# POWERAMP.net
KiCad netlist of a schematic drawn in Altium Designer
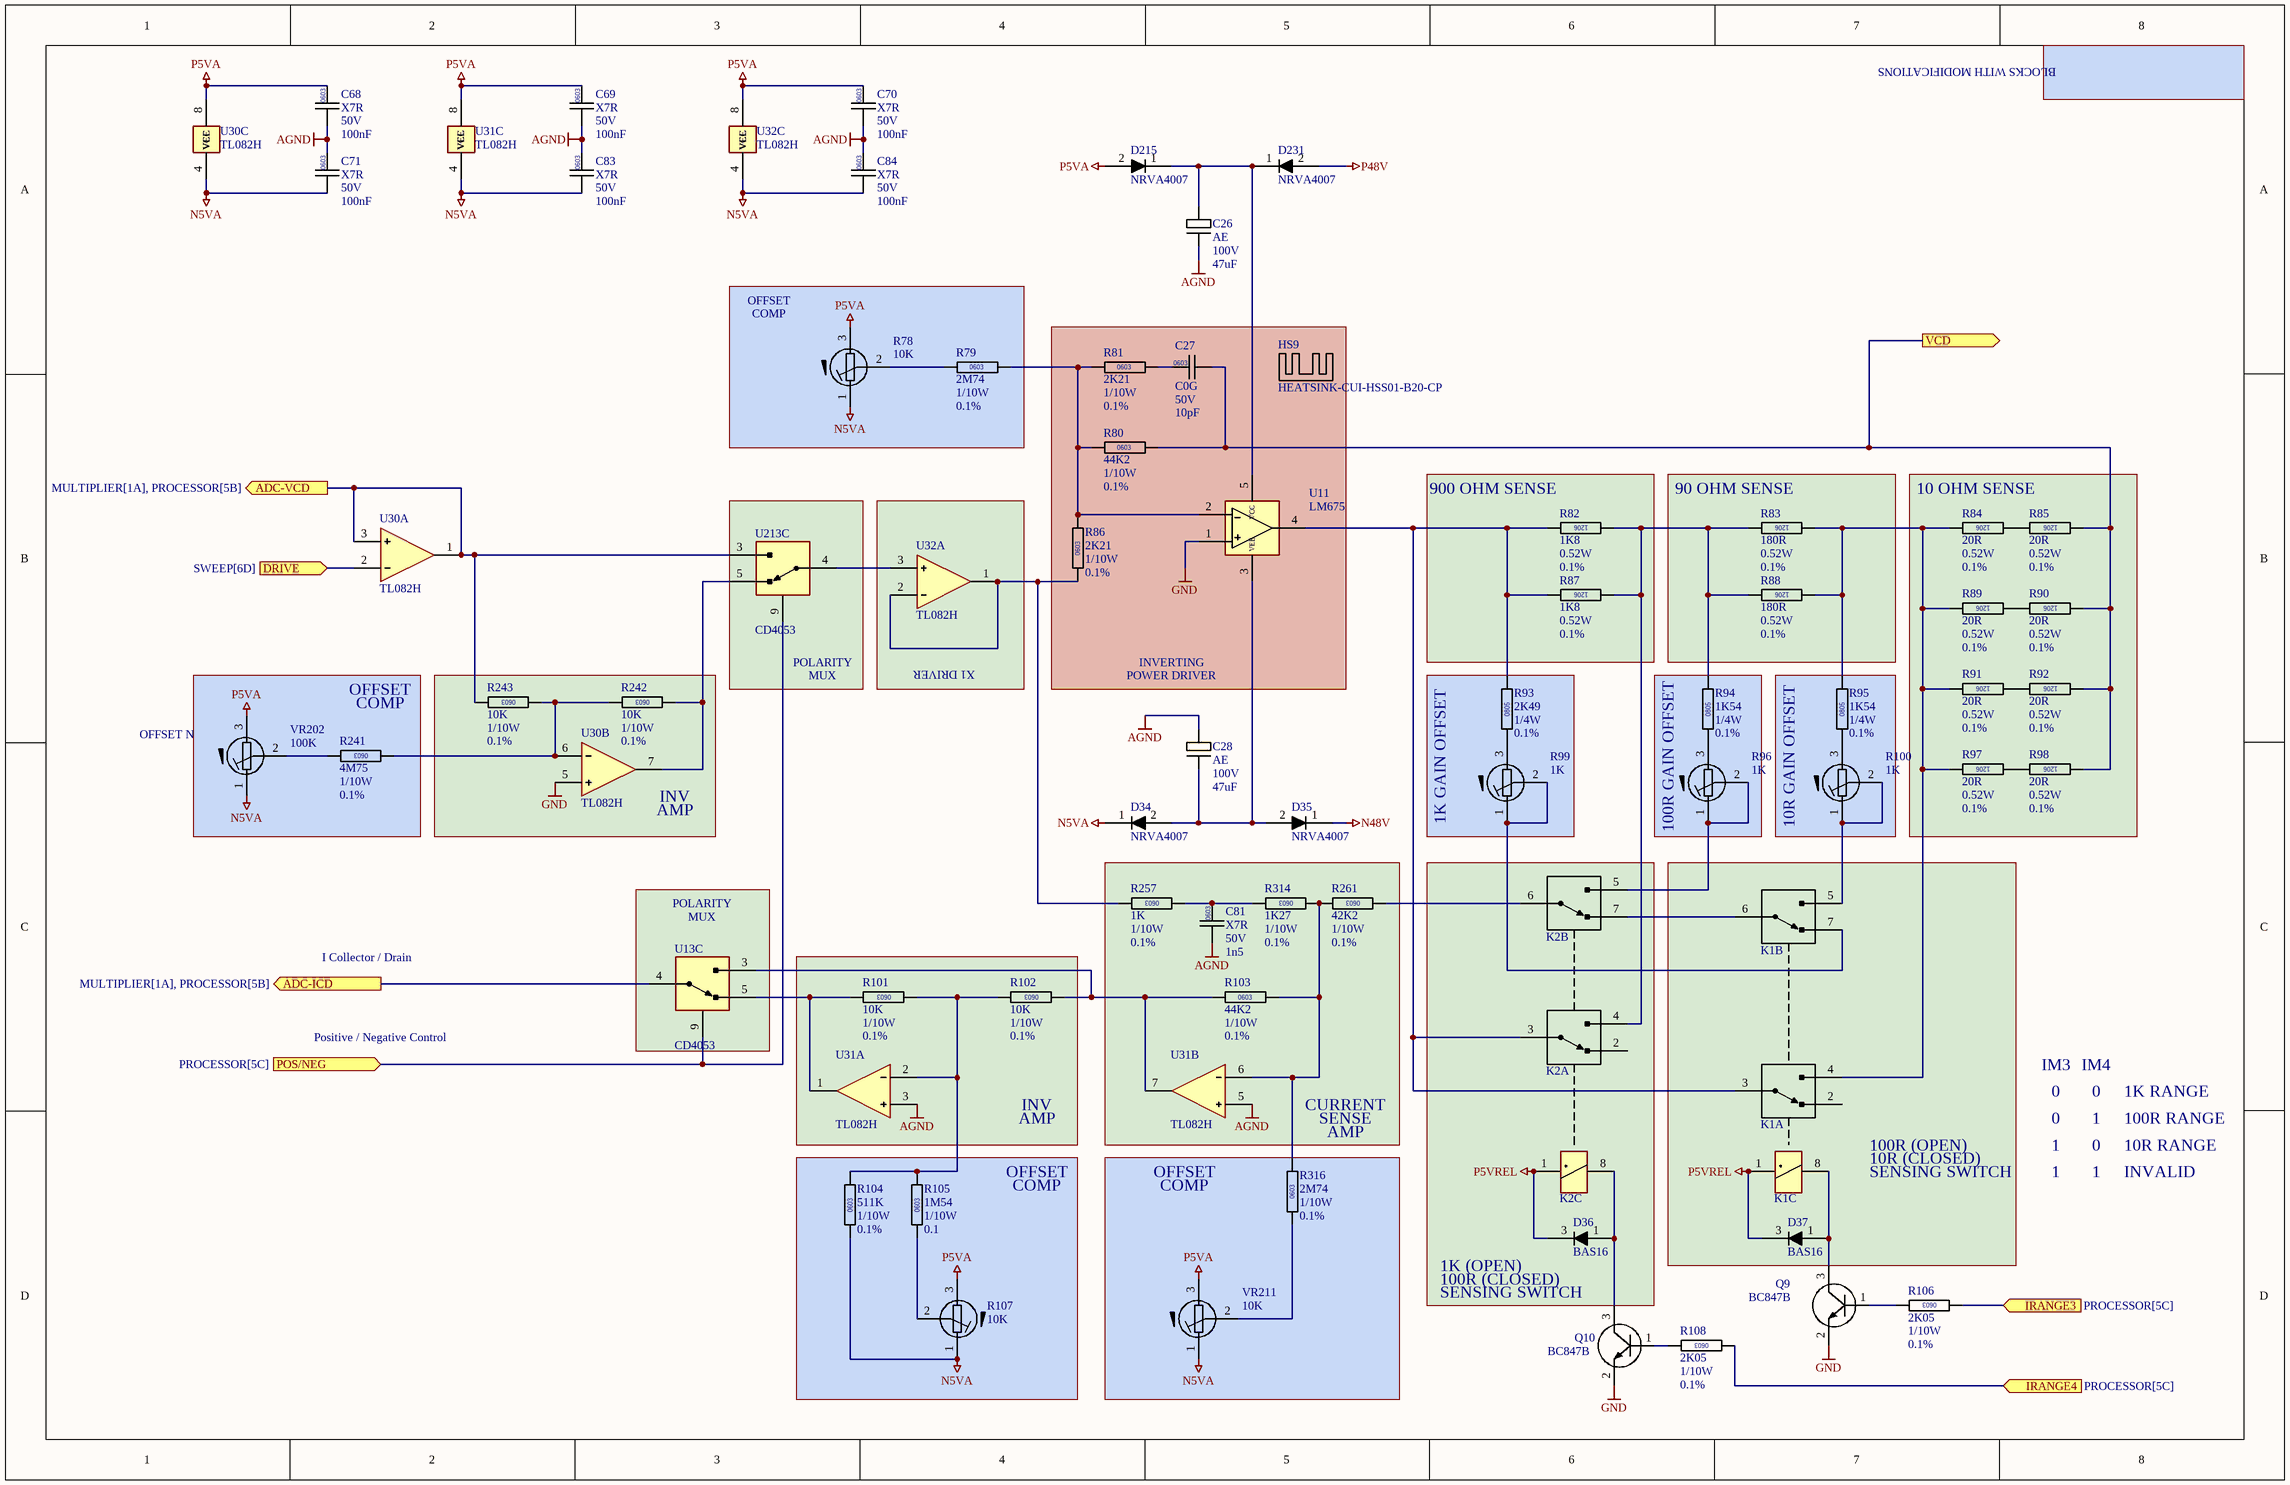
[diagram p0: POWERAMP.SchDoc]

(export (version "E")
  (design (tool "Eeschema 10.0.6"))
  (components
    (comp (ref "C26")
      (value "CAP0603")
      (footprint "CAPAE-KEMET-ESL476M100AH9AA")
      (description "CAPACITOR,ALU,47uF,100V,TH,P5mm,D10mm,H14mm")
      (fields
        (field (name "DIELECTRIC") "AE")
        (field (name "VOLTAGE") "100V")
        (field (name "CAPACITANCE") "47uF")
      )
      (libsource (lib "CAPACITORS") (part "CAPP-AE-47uF-100V-TH050P100D140H"))
    )
    (comp (ref "C27")
      (value "CAP0603")
      (footprint "CAPC0603")
      (description "CAPACITOR,CERAMIC,10pF,50V,C0G,0603")
      (fields
        (field (name "DIELECTRIC") "C0G")
        (field (name "VOLTAGE") "50V")
        (field (name "CAPACITANCE") "10pF")
      )
      (libsource (lib "CAPACITORS") (part "CAPC-0603-10PF-50V-C0G"))
    )
    (comp (ref "C28")
      (value "CAP0603")
      (footprint "CAPAE-KEMET-ESL476M100AH9AA")
      (description "CAPACITOR,ALU,47uF,100V,TH,P5mm,D10mm,H14mm")
      (fields
        (field (name "DIELECTRIC") "AE")
        (field (name "VOLTAGE") "100V")
        (field (name "CAPACITANCE") "47uF")
      )
      (libsource (lib "CAPACITORS") (part "CAPP-AE-47uF-100V-TH050P100D140H"))
    )
    (comp (ref "C68")
      (value "CAP0603")
      (footprint "CAPC0603")
      (description "CAPACITOR,CERAMIC,100nF,50V,X7R,0603")
      (fields
        (field (name "DIELECTRIC") "X7R")
        (field (name "VOLTAGE") "50V")
        (field (name "CAPACITANCE") "100nF")
      )
      (libsource (lib "CAPACITORS") (part "CAPC-0603-100nF-50V-X7R"))
    )
    (comp (ref "C69")
      (value "CAP0603")
      (footprint "CAPC0603")
      (description "CAPACITOR,CERAMIC,100nF,50V,X7R,0603")
      (fields
        (field (name "DIELECTRIC") "X7R")
        (field (name "VOLTAGE") "50V")
        (field (name "CAPACITANCE") "100nF")
      )
      (libsource (lib "CAPACITORS") (part "CAPC-0603-100nF-50V-X7R"))
    )
    (comp (ref "C70")
      (value "CAP0603")
      (footprint "CAPC0603")
      (description "CAPACITOR,CERAMIC,100nF,50V,X7R,0603")
      (fields
        (field (name "DIELECTRIC") "X7R")
        (field (name "VOLTAGE") "50V")
        (field (name "CAPACITANCE") "100nF")
      )
      (libsource (lib "CAPACITORS") (part "CAPC-0603-100nF-50V-X7R"))
    )
    (comp (ref "C71")
      (value "CAP0603")
      (footprint "CAPC0603")
      (description "CAPACITOR,CERAMIC,100nF,50V,X7R,0603")
      (fields
        (field (name "DIELECTRIC") "X7R")
        (field (name "VOLTAGE") "50V")
        (field (name "CAPACITANCE") "100nF")
      )
      (libsource (lib "CAPACITORS") (part "CAPC-0603-100nF-50V-X7R"))
    )
    (comp (ref "C81")
      (value "CAP0603")
      (footprint "CAPC0603")
      (description "CAPACITOR,CERAMIC,1n5,50V,X7R,0603")
      (fields
        (field (name "DIELECTRIC") "X7R")
        (field (name "VOLTAGE") "50V")
        (field (name "CAPACITANCE") "1n5")
      )
      (libsource (lib "CAPACITORS") (part "CAPC-0603-1n5-50V-X7R"))
    )
    (comp (ref "C83")
      (value "CAP0603")
      (footprint "CAPC0603")
      (description "CAPACITOR,CERAMIC,100nF,50V,X7R,0603")
      (fields
        (field (name "DIELECTRIC") "X7R")
        (field (name "VOLTAGE") "50V")
        (field (name "CAPACITANCE") "100nF")
      )
      (libsource (lib "CAPACITORS") (part "CAPC-0603-100nF-50V-X7R"))
    )
    (comp (ref "C84")
      (value "CAP0603")
      (footprint "CAPC0603")
      (description "CAPACITOR,CERAMIC,100nF,50V,X7R,0603")
      (fields
        (field (name "DIELECTRIC") "X7R")
        (field (name "VOLTAGE") "50V")
        (field (name "CAPACITANCE") "100nF")
      )
      (libsource (lib "CAPACITORS") (part "CAPC-0603-100nF-50V-X7R"))
    )
    (comp (ref "D34")
      (value "NRVA4007")
      (footprint "DO214AC")
      (description "DIODE,RECTIFIER,1000V,1A,ONSEMI,NRVA4007,SMA")
      (libsource (lib "DIODES") (part "DIODE-ONSEMI-NRVA4007T3G"))
    )
    (comp (ref "D35")
      (value "NRVA4007")
      (footprint "DO214AC")
      (description "DIODE,RECTIFIER,1000V,1A,ONSEMI,NRVA4007,SMA")
      (libsource (lib "DIODES") (part "DIODE-ONSEMI-NRVA4007T3G"))
    )
    (comp (ref "D36")
      (value "BAS16")
      (footprint "SOT23")
      (description "DIODE,RECTIFIER,75V,0.3A,BAS16,SOT23")
      (libsource (lib "DIODES") (part "DIODE-RECTIFIER-DIODES-BAS16-SOT23"))
    )
    (comp (ref "D37")
      (value "BAS16")
      (footprint "SOT23")
      (description "DIODE,RECTIFIER,75V,0.3A,BAS16,SOT23")
      (libsource (lib "DIODES") (part "DIODE-RECTIFIER-DIODES-BAS16-SOT23"))
    )
    (comp (ref "D215")
      (value "NRVA4007")
      (footprint "DO214AC")
      (description "DIODE,RECTIFIER,1000V,1A,ONSEMI,NRVA4007,SMA")
      (libsource (lib "DIODES") (part "DIODE-ONSEMI-NRVA4007T3G"))
    )
    (comp (ref "D231")
      (value "NRVA4007")
      (footprint "DO214AC")
      (description "DIODE,RECTIFIER,1000V,1A,ONSEMI,NRVA4007,SMA")
      (libsource (lib "DIODES") (part "DIODE-ONSEMI-NRVA4007T3G"))
    )
    (comp (ref "HS9")
      (value "HEATSINK-CUI-HSS01-B20-CP")
      (footprint "HEATSINK-CUI-HSS01-B20-CP")
      (description "HEATSINKSTAMPED,CLIP-ON,BOARDMOUNT,3W,25C/W,CUI,HSS01-B20-CP")
      (libsource (lib "HEATSINK") (part "HEATSINK-CUI-HSS01-B20-CP"))
    )
    (comp (ref "K1")
      (value "RELAY-KEMET-UA2-5NJ")
      (footprint "RELAY-KEMET-UA2-5NJ")
      (description "RELAY,DPDT,1A,250VAC,220VDC,5V COIL,KEMET,UA2-5NJ")
      (libsource (lib "RELAYS") (part "RELAY-KEMET-UA2-5NJ"))
    )
    (comp (ref "K2")
      (value "RELAY-KEMET-UA2-5NJ")
      (footprint "RELAY-KEMET-UA2-5NJ")
      (description "RELAY,DPDT,1A,250VAC,220VDC,5V COIL,KEMET,UA2-5NJ")
      (libsource (lib "") (part "RELAY-KEMET-UA2-5NJ_1"))
    )
    (comp (ref "Q9")
      (value "BC847B")
      (footprint "SOT23")
      (description "XSTR,NPN,45V,0.1A,,BC847B,SOT23")
      (libsource (lib "TRANSISTORS") (part "XSTR-NPN-BC847"))
    )
    (comp (ref "Q10")
      (value "BC847B")
      (footprint "SOT23")
      (description "XSTR,NPN,45V,0.1A,,BC847B,SOT23")
      (libsource (lib "TRANSISTORS") (part "XSTR-NPN-BC847"))
    )
    (comp (ref "R78")
      (value "10K")
      (footprint "TRIMMER-BOURNS-3214X")
      (description "RESISTOR,MULTITURN,VERTICAL,5T,10K")
      (fields (field (name "Comment") "TRIMMER-BOURNS-3214X-1-103E"))
      (libsource (lib "RESISTORS") (part "TRIMMER-BOURNS-3214X-1-103E"))
    )
    (comp (ref "R79")
      (value "2M74")
      (footprint "RESC0603")
      (description "RESISTOR,2M74,0.1%,100mW,0603 (1608)")
      (fields
        (field (name "POWER") "1/10W")
        (field (name "TOLERANCE") "0.1%")
        (field (name "Comment") "RESC0603")
      )
      (libsource (lib "RESISTORS") (part "RESC-0603-2M74-0.1%-1/10W"))
    )
    (comp (ref "R80")
      (value "44K2")
      (footprint "RESC0603")
      (description "RESISTOR,44K2,0.1%,100mW,0603 (1608)")
      (fields
        (field (name "POWER") "1/10W")
        (field (name "TOLERANCE") "0.1%")
        (field (name "Comment") "RESC0603")
      )
      (libsource (lib "RESISTORS") (part "RESC-0603-44K2-0.1%-1/10W"))
    )
    (comp (ref "R81")
      (value "2K21")
      (footprint "RESC0603")
      (description "RESISTOR,2K21,0.1%,100mW,0603 (1608)")
      (fields
        (field (name "POWER") "1/10W")
        (field (name "TOLERANCE") "0.1%")
        (field (name "Comment") "RESC0603")
      )
      (libsource (lib "RESISTORS") (part "RESC-0603-2K21-0.1%-1/10W"))
    )
    (comp (ref "R82")
      (value "1K8")
      (footprint "RESC1206")
      (description "RESISTOR,1K8,1206,0.1%,520mW,1206")
      (fields
        (field (name "POWER") "0.52W")
        (field (name "TOLERANCE") "0.1%")
        (field (name "Comment") "RESC1206")
      )
      (libsource (lib "RESISTORS") (part "RESC-1206-1K8-0.1%-1/2W"))
    )
    (comp (ref "R83")
      (value "180R")
      (footprint "RESC1206")
      (description "RESISTOR,180,1206,0.1%,520mW,1206")
      (fields
        (field (name "POWER") "0.52W")
        (field (name "TOLERANCE") "0.1%")
        (field (name "Comment") "RESC1206")
      )
      (libsource (lib "RESISTORS") (part "RESC-1206-180R-0.1%-1/2W"))
    )
    (comp (ref "R84")
      (value "20R")
      (footprint "RESC1206")
      (description "RESISTOR,20R,1206,0.1%,520mW,1206")
      (fields
        (field (name "POWER") "0.52W")
        (field (name "TOLERANCE") "0.1%")
        (field (name "Comment") "RESC1206")
      )
      (libsource (lib "RESISTORS") (part "RESC-1206-20R-0.1%-1/2W"))
    )
    (comp (ref "R85")
      (value "20R")
      (footprint "RESC1206")
      (description "RESISTOR,20R,1206,0.1%,520mW,1206")
      (fields
        (field (name "POWER") "0.52W")
        (field (name "TOLERANCE") "0.1%")
        (field (name "Comment") "RESC1206")
      )
      (libsource (lib "RESISTORS") (part "RESC-1206-20R-0.1%-1/2W"))
    )
    (comp (ref "R86")
      (value "2K21")
      (footprint "RESC0603")
      (description "RESISTOR,2K21,0.1%,100mW,0603 (1608)")
      (fields
        (field (name "POWER") "1/10W")
        (field (name "TOLERANCE") "0.1%")
        (field (name "Comment") "RESC0603")
      )
      (libsource (lib "RESISTORS") (part "RESC-0603-2K21-0.1%-1/10W"))
    )
    (comp (ref "R87")
      (value "1K8")
      (footprint "RESC1206")
      (description "RESISTOR,1K8,1206,0.1%,520mW,1206")
      (fields
        (field (name "POWER") "0.52W")
        (field (name "TOLERANCE") "0.1%")
        (field (name "Comment") "RESC1206")
      )
      (libsource (lib "RESISTORS") (part "RESC-1206-1K8-0.1%-1/2W"))
    )
    (comp (ref "R88")
      (value "180R")
      (footprint "RESC1206")
      (description "RESISTOR,180,1206,0.1%,520mW,1206")
      (fields
        (field (name "POWER") "0.52W")
        (field (name "TOLERANCE") "0.1%")
        (field (name "Comment") "RESC1206")
      )
      (libsource (lib "RESISTORS") (part "RESC-1206-180R-0.1%-1/2W"))
    )
    (comp (ref "R89")
      (value "20R")
      (footprint "RESC1206")
      (description "RESISTOR,20R,1206,0.1%,520mW,1206")
      (fields
        (field (name "POWER") "0.52W")
        (field (name "TOLERANCE") "0.1%")
        (field (name "Comment") "RESC1206")
      )
      (libsource (lib "RESISTORS") (part "RESC-1206-20R-0.1%-1/2W"))
    )
    (comp (ref "R90")
      (value "20R")
      (footprint "RESC1206")
      (description "RESISTOR,20R,1206,0.1%,520mW,1206")
      (fields
        (field (name "POWER") "0.52W")
        (field (name "TOLERANCE") "0.1%")
        (field (name "Comment") "RESC1206")
      )
      (libsource (lib "RESISTORS") (part "RESC-1206-20R-0.1%-1/2W"))
    )
    (comp (ref "R91")
      (value "20R")
      (footprint "RESC1206")
      (description "RESISTOR,20R,1206,0.1%,520mW,1206")
      (fields
        (field (name "POWER") "0.52W")
        (field (name "TOLERANCE") "0.1%")
        (field (name "Comment") "RESC1206")
      )
      (libsource (lib "RESISTORS") (part "RESC-1206-20R-0.1%-1/2W"))
    )
    (comp (ref "R92")
      (value "20R")
      (footprint "RESC1206")
      (description "RESISTOR,20R,1206,0.1%,520mW,1206")
      (fields
        (field (name "POWER") "0.52W")
        (field (name "TOLERANCE") "0.1%")
        (field (name "Comment") "RESC1206")
      )
      (libsource (lib "RESISTORS") (part "RESC-1206-20R-0.1%-1/2W"))
    )
    (comp (ref "R93")
      (value "2K49")
      (footprint "RESC0805")
      (description "RESISTOR,2K49,0.1%,250mW,0805")
      (fields
        (field (name "POWER") "1/4W")
        (field (name "TOLERANCE") "0.1%")
        (field (name "Comment") "RESC0805")
      )
      (libsource (lib "RESISTORS") (part "RESC-0805-2K49-0.1%-1/4W"))
    )
    (comp (ref "R94")
      (value "1K54")
      (footprint "RESC0805")
      (description "RESISTOR,1K54,0.1%,250mW,0805")
      (fields
        (field (name "POWER") "1/4W")
        (field (name "TOLERANCE") "0.1%")
        (field (name "Comment") "RESC0805")
      )
      (libsource (lib "RESISTORS") (part "RESC-0805-1K54-0.1%-1/4W"))
    )
    (comp (ref "R95")
      (value "1K54")
      (footprint "RESC0805")
      (description "RESISTOR,1K54,0.1%,250mW,0805")
      (fields
        (field (name "POWER") "1/4W")
        (field (name "TOLERANCE") "0.1%")
        (field (name "Comment") "RESC0805")
      )
      (libsource (lib "RESISTORS") (part "RESC-0805-1K54-0.1%-1/4W"))
    )
    (comp (ref "R96")
      (value "1K")
      (footprint "TRIMMER-BOURNS-3214X")
      (description "RESISTOR,MULTITURN,VERTICAL,5T,1K")
      (fields (field (name "Comment") "TRIMMER-BOURNS-3214X-1-102E"))
      (libsource (lib "RESISTORS") (part "TRIMMER-BOURNS-3214X-1-102E"))
    )
    (comp (ref "R97")
      (value "20R")
      (footprint "RESC1206")
      (description "RESISTOR,20R,1206,0.1%,520mW,1206")
      (fields
        (field (name "POWER") "0.52W")
        (field (name "TOLERANCE") "0.1%")
        (field (name "Comment") "RESC1206")
      )
      (libsource (lib "RESISTORS") (part "RESC-1206-20R-0.1%-1/2W"))
    )
    (comp (ref "R98")
      (value "20R")
      (footprint "RESC1206")
      (description "RESISTOR,20R,1206,0.1%,520mW,1206")
      (fields
        (field (name "POWER") "0.52W")
        (field (name "TOLERANCE") "0.1%")
        (field (name "Comment") "RESC1206")
      )
      (libsource (lib "RESISTORS") (part "RESC-1206-20R-0.1%-1/2W"))
    )
    (comp (ref "R99")
      (value "1K")
      (footprint "TRIMMER-BOURNS-3214X")
      (description "RESISTOR,MULTITURN,VERTICAL,5T,1K")
      (fields (field (name "Comment") "TRIMMER-BOURNS-3214X-1-102E"))
      (libsource (lib "RESISTORS") (part "TRIMMER-BOURNS-3214X-1-102E"))
    )
    (comp (ref "R100")
      (value "1K")
      (footprint "TRIMMER-BOURNS-3214X")
      (description "RESISTOR,MULTITURN,VERTICAL,5T,1K")
      (fields (field (name "Comment") "TRIMMER-BOURNS-3214X-1-102E"))
      (libsource (lib "RESISTORS") (part "TRIMMER-BOURNS-3214X-1-102E"))
    )
    (comp (ref "R101")
      (value "10K")
      (footprint "RESC0603")
      (description "RESISTOR,10K,0.1%,100mW,0603 (1608)")
      (fields
        (field (name "POWER") "1/10W")
        (field (name "TOLERANCE") "0.1%")
        (field (name "Comment") "RESC0603")
      )
      (libsource (lib "RESISTORS") (part "RESC-0603-10K-0.1%-1/10W"))
    )
    (comp (ref "R102")
      (value "10K")
      (footprint "RESC0603")
      (description "RESISTOR,10K,0.1%,100mW,0603 (1608)")
      (fields
        (field (name "POWER") "1/10W")
        (field (name "TOLERANCE") "0.1%")
        (field (name "Comment") "RESC0603")
      )
      (libsource (lib "RESISTORS") (part "RESC-0603-10K-0.1%-1/10W"))
    )
    (comp (ref "R103")
      (value "44K2")
      (footprint "RESC0603")
      (description "RESISTOR,44K2,0.1%,100mW,0603 (1608)")
      (fields
        (field (name "POWER") "1/10W")
        (field (name "TOLERANCE") "0.1%")
        (field (name "Comment") "RESC0603")
      )
      (libsource (lib "RESISTORS") (part "RESC-0603-44K2-0.1%-1/10W"))
    )
    (comp (ref "R104")
      (value "511K")
      (footprint "RESC0603")
      (description "RESISTOR,511K,0.1%,100mW,0603 (1608)")
      (fields
        (field (name "POWER") "1/10W")
        (field (name "TOLERANCE") "0.1%")
        (field (name "Comment") "RESC0603")
      )
      (libsource (lib "RESISTORS") (part "RESC-0603-511K-0.1%-1/10W"))
    )
    (comp (ref "R105")
      (value "1M54")
      (footprint "RESC0603")
      (description "RESISTOR,1M54,0.1%,100mW,0603 (1608)")
      (fields
        (field (name "POWER") "1/10W")
        (field (name "TOLERANCE") "0.1")
        (field (name "Comment") "RESC0603")
      )
      (libsource (lib "RESISTORS") (part "RESC-0603-1M54-0.1%-1/10W"))
    )
    (comp (ref "R106")
      (value "2K05")
      (footprint "RESC0603")
      (description "RESISTOR,2K05,0.11%,100mW,0603 (1608)")
      (fields
        (field (name "POWER") "1/10W")
        (field (name "TOLERANCE") "0.1%")
        (field (name "Comment") "RESC0603")
      )
      (libsource (lib "RESISTORS") (part "RESC-0603-2K05-0.1%-1/10W"))
    )
    (comp (ref "R107")
      (value "10K")
      (footprint "TRIMMER-BOURNS-3214X")
      (description "RESISTOR,MULTITURN,VERTICAL,5T,10K")
      (fields (field (name "Comment") "TRIMMER-BOURNS-3214X-1-103E"))
      (libsource (lib "RESISTORS") (part "TRIMMER-BOURNS-3214X-1-103E"))
    )
    (comp (ref "R108")
      (value "2K05")
      (footprint "RESC0603")
      (description "RESISTOR,2K05,0.11%,100mW,0603 (1608)")
      (fields
        (field (name "POWER") "1/10W")
        (field (name "TOLERANCE") "0.1%")
        (field (name "Comment") "RESC0603")
      )
      (libsource (lib "RESISTORS") (part "RESC-0603-2K05-0.1%-1/10W"))
    )
    (comp (ref "R241")
      (value "4M75")
      (footprint "RESC0603")
      (description "RESISTOR,4M75,0.1%,100mW,0603 (1608)")
      (fields
        (field (name "POWER") "1/10W")
        (field (name "TOLERANCE") "0.1%")
        (field (name "Comment") "RESC0603")
      )
      (libsource (lib "RESISTORS") (part "RESC-0603-4M75-1%-1/10W"))
    )
    (comp (ref "R242")
      (value "10K")
      (footprint "RESC0603")
      (description "RESISTOR,10K,0.1%,100mW,0603 (1608)")
      (fields
        (field (name "POWER") "1/10W")
        (field (name "TOLERANCE") "0.1%")
        (field (name "Comment") "RESC0603")
      )
      (libsource (lib "RESISTORS") (part "RESC-0603-10K-0.1%-1/10W"))
    )
    (comp (ref "R243")
      (value "10K")
      (footprint "RESC0603")
      (description "RESISTOR,10K,0.1%,100mW,0603 (1608)")
      (fields
        (field (name "POWER") "1/10W")
        (field (name "TOLERANCE") "0.1%")
        (field (name "Comment") "RESC0603")
      )
      (libsource (lib "RESISTORS") (part "RESC-0603-10K-0.1%-1/10W"))
    )
    (comp (ref "R257")
      (value "1K")
      (footprint "RESC0603")
      (description "RESISTOR,1K,0.1%,100mW,0603 (1608)")
      (fields
        (field (name "POWER") "1/10W")
        (field (name "TOLERANCE") "0.1%")
        (field (name "Comment") "RESC0603")
      )
      (libsource (lib "RESISTORS") (part "RESC-0603-1K-0.1%-1/10W"))
    )
    (comp (ref "R261")
      (value "42K2")
      (footprint "RESC0603")
      (description "RESISTOR,42K2,0.1%,100mW,0603 (1608)")
      (fields
        (field (name "POWER") "1/10W")
        (field (name "TOLERANCE") "0.1%")
        (field (name "Comment") "RESC0603")
      )
      (libsource (lib "RESISTORS") (part "RESC-0603-42K2-0.1%-1/10W"))
    )
    (comp (ref "R314")
      (value "1K27")
      (footprint "RESC0603")
      (description "RESISTOR,1K27,0.1%,100mW,0603 (1608)")
      (fields
        (field (name "POWER") "1/10W")
        (field (name "TOLERANCE") "0.1%")
        (field (name "Comment") "RESC0603")
      )
      (libsource (lib "RESISTORS") (part "RESC-0603-1K27-0.1%-1/10W"))
    )
    (comp (ref "R316")
      (value "2M74")
      (footprint "RESC0603")
      (description "RESISTOR,2M74,0.1%,100mW,0603 (1608)")
      (fields
        (field (name "POWER") "1/10W")
        (field (name "TOLERANCE") "0.1%")
        (field (name "Comment") "RESC0603")
      )
      (libsource (lib "RESISTORS") (part "RESC-0603-2M74-0.1%-1/10W"))
    )
    (comp (ref "U11")
      (value "LM675")
      (footprint "TO220-5-V")
      (description "IC,OPAMP,SINGLE,POWER,LM675,TO220-5")
      (libsource (lib "IC-OPAMP") (part "IC-TI-LM675-TO220-5"))
    )
    (comp (ref "U13")
      (value "CD4053")
      (footprint "SO127P600-16N")
      (description "IC,LOGIC,CMOS,4XXX,TRIPLE 2:1 MUX,SPLIT BLOCKS")
      (libsource (lib "") (part "IC-TI-CD4053-SPLIT_1"))
    )
    (comp (ref "U30")
      (value "TL082H")
      (footprint "SO127P600-8N")
      (description "IC,OPAMP JFET,DUAL,TL082HIDR,SO8")
      (libsource (lib "") (part "IC-TI-TL082H-SO8_1"))
    )
    (comp (ref "U31")
      (value "TL082H")
      (footprint "SO127P600-8N")
      (description "IC,OPAMP JFET,DUAL,TL082HIDR,SO8")
      (libsource (lib "") (part "IC-TI-TL082H-SO8_2"))
    )
    (comp (ref "U32")
      (value "TL082H")
      (footprint "SO127P600-8N")
      (description "IC,OPAMP JFET,DUAL,TL082HIDR,SO8")
      (libsource (lib "IC-OPAMP") (part "IC-TI-TL082H-SO8"))
    )
    (comp (ref "U213")
      (value "CD4053")
      (footprint "SO127P600-16N")
      (description "IC,LOGIC,CMOS,4XXX,TRIPLE 2:1 MUX,SPLIT BLOCKS")
      (libsource (lib "IC-4XXX") (part "IC-TI-CD4053-SPLIT"))
    )
    (comp (ref "VR202")
      (value "100K")
      (footprint "TRIMMER-BOURNS-3214X")
      (description "RESISTOR,MULTITURN,VERTICAL,5T,100K")
      (fields (field (name "Comment") "TRIMMER-BOURNS-3214X-1-104"))
      (libsource (lib "RESISTORS") (part "TRIMMER-BOURNS-3214X-1-104"))
    )
    (comp (ref "VR211")
      (value "10K")
      (footprint "TRIMMER-BOURNS-3214X")
      (description "RESISTOR,MULTITURN,VERTICAL,5T,10K")
      (fields (field (name "Comment") "TRIMMER-BOURNS-3214X-1-103E"))
      (libsource (lib "RESISTORS") (part "TRIMMER-BOURNS-3214X-1-103E"))
    )
  )
  (nets
    (net (code "1") (name "/ADC-ICD") (class "Default")
      (node (ref "U13") (pin "4") (pinfunction "Y3_4") (pintype "passive"))
    )
    (net (code "2") (name "/ADC-VCD") (class "Default")
      (node (ref "R243") (pin "1") (pintype "passive"))
      (node (ref "U213") (pin "3") (pinfunction "Y_3") (pintype "passive"))
      (node (ref "U30") (pin "1") (pinfunction "O_1") (pintype "passive"))
      (node (ref "U30") (pin "3") (pinfunction "+_3") (pintype "passive"))
    )
    (net (code "3") (name "/DRIVE") (class "Default")
      (node (ref "U30") (pin "2") (pinfunction "-_2") (pintype "passive"))
    )
    (net (code "4") (name "/IRANGE3") (class "Default") (node (ref "R106") (pin "1") (pintype "passive")))
    (net (code "5") (name "/IRANGE4") (class "Default") (node (ref "R108") (pin "1") (pintype "passive")))
    (net (code "6") (name "/POS{slash}NEG") (class "Default")
      (node (ref "U13") (pin "9") (pinfunction "B_9") (pintype "passive"))
      (node (ref "U213") (pin "9") (pinfunction "B_9") (pintype "passive"))
    )
    (net (code "7") (name "/VCD") (class "Default")
      (node (ref "C27") (pin "2") (pintype "passive"))
      (node (ref "R80") (pin "2") (pintype "passive"))
      (node (ref "R85") (pin "2") (pintype "passive"))
      (node (ref "R90") (pin "2") (pintype "passive"))
      (node (ref "R92") (pin "2") (pintype "passive"))
      (node (ref "R98") (pin "2") (pintype "passive"))
    )
    (net (code "8") (name "AGND") (class "Default")
      (node (ref "C26") (pin "2") (pintype "passive"))
      (node (ref "C28") (pin "1") (pintype "passive"))
      (node (ref "C68") (pin "2") (pintype "passive"))
      (node (ref "C69") (pin "2") (pintype "passive"))
      (node (ref "C70") (pin "2") (pintype "passive"))
      (node (ref "C71") (pin "1") (pintype "passive"))
      (node (ref "C81") (pin "2") (pintype "passive"))
      (node (ref "C83") (pin "1") (pintype "passive"))
      (node (ref "C84") (pin "1") (pintype "passive"))
      (node (ref "U31") (pin "3") (pinfunction "+_3") (pintype "passive"))
      (node (ref "U31") (pin "5") (pinfunction "+_5") (pintype "passive"))
    )
    (net (code "9") (name "GND") (class "Default")
      (node (ref "Q10") (pin "2") (pinfunction "E_2") (pintype "passive"))
      (node (ref "Q9") (pin "2") (pinfunction "E_2") (pintype "passive"))
      (node (ref "U11") (pin "1") (pinfunction "+_1") (pintype "passive"))
      (node (ref "U30") (pin "5") (pinfunction "+_5") (pintype "passive"))
    )
    (net (code "10") (name "N5VA") (class "Default")
      (node (ref "C71") (pin "2") (pintype "passive"))
      (node (ref "C83") (pin "2") (pintype "passive"))
      (node (ref "C84") (pin "2") (pintype "passive"))
      (node (ref "D34") (pin "1") (pinfunction "K_1") (pintype "passive"))
      (node (ref "R104") (pin "2") (pintype "passive"))
      (node (ref "R107") (pin "1") (pinfunction "1_1") (pintype "passive"))
      (node (ref "R78") (pin "1") (pinfunction "1_1") (pintype "passive"))
      (node (ref "U30") (pin "4") (pinfunction "VEE_4") (pintype "passive"))
      (node (ref "U31") (pin "4") (pinfunction "VEE_4") (pintype "passive"))
      (node (ref "U32") (pin "4") (pinfunction "VEE_4") (pintype "passive"))
      (node (ref "VR202") (pin "1") (pinfunction "1_1") (pintype "passive"))
      (node (ref "VR211") (pin "1") (pinfunction "1_1") (pintype "passive"))
    )
    (net (code "11") (name "N48V") (class "Default")
      (node (ref "D35") (pin "1") (pinfunction "K_1") (pintype "passive"))
    )
    (net (code "12") (name "Net-(C27-Pad1)") (class "Default")
      (node (ref "C27") (pin "1") (pintype "passive"))
      (node (ref "R81") (pin "2") (pintype "passive"))
    )
    (net (code "13") (name "Net-(C81-Pad1)") (class "Default")
      (node (ref "C81") (pin "1") (pintype "passive"))
      (node (ref "R257") (pin "2") (pintype "passive"))
      (node (ref "R314") (pin "1") (pintype "passive"))
    )
    (net (code "14") (name "Net-(D34-A)") (class "Default")
      (node (ref "C28") (pin "2") (pintype "passive"))
      (node (ref "D34") (pin "2") (pinfunction "A_2") (pintype "passive"))
      (node (ref "D35") (pin "2") (pinfunction "A_2") (pintype "passive"))
      (node (ref "U11") (pin "3") (pinfunction "VEE_3") (pintype "passive"))
    )
    (net (code "15") (name "Net-(D36-A)") (class "Default")
      (node (ref "D36") (pin "1") (pinfunction "A_1") (pintype "passive"))
      (node (ref "K2") (pin "8") (pinfunction "8_8") (pintype "passive"))
      (node (ref "Q10") (pin "3") (pinfunction "C_3") (pintype "passive"))
    )
    (net (code "16") (name "Net-(D37-A)") (class "Default")
      (node (ref "D37") (pin "1") (pinfunction "A_1") (pintype "passive"))
      (node (ref "K1") (pin "8") (pinfunction "8_8") (pintype "passive"))
      (node (ref "Q9") (pin "3") (pinfunction "C_3") (pintype "passive"))
    )
    (net (code "17") (name "Net-(D215-K)") (class "Default")
      (node (ref "C26") (pin "1") (pintype "passive"))
      (node (ref "D215") (pin "1") (pinfunction "K_1") (pintype "passive"))
      (node (ref "D231") (pin "1") (pinfunction "K_1") (pintype "passive"))
      (node (ref "U11") (pin "5") (pinfunction "VCC_5") (pintype "passive"))
    )
    (net (code "18") (name "Net-(K1A-COM)") (class "Default")
      (node (ref "K1") (pin "3") (pinfunction "COM_3") (pintype "passive"))
      (node (ref "K2") (pin "3") (pinfunction "COM_3") (pintype "passive"))
      (node (ref "R82") (pin "1") (pintype "passive"))
      (node (ref "R87") (pin "1") (pintype "passive"))
      (node (ref "R93") (pin "1") (pintype "passive"))
      (node (ref "U11") (pin "4") (pinfunction "OUT_4") (pintype "passive"))
    )
    (net (code "19") (name "Net-(K1A-NO)") (class "Default")
      (node (ref "K1") (pin "4") (pinfunction "NO_4") (pintype "passive"))
      (node (ref "R83") (pin "2") (pintype "passive"))
      (node (ref "R84") (pin "1") (pintype "passive"))
      (node (ref "R88") (pin "2") (pintype "passive"))
      (node (ref "R89") (pin "1") (pintype "passive"))
      (node (ref "R91") (pin "1") (pintype "passive"))
      (node (ref "R95") (pin "2") (pintype "passive"))
      (node (ref "R97") (pin "1") (pintype "passive"))
    )
    (net (code "20") (name "Net-(K1B-COM)") (class "Default")
      (node (ref "K1") (pin "6") (pinfunction "COM_6") (pintype "passive"))
      (node (ref "K2") (pin "7") (pinfunction "NC_7") (pintype "passive"))
    )
    (net (code "21") (name "Net-(K1B-NC)") (class "Default")
      (node (ref "K1") (pin "7") (pinfunction "NC_7") (pintype "passive"))
      (node (ref "R99") (pin "1") (pinfunction "1_1") (pintype "passive"))
      (node (ref "R99") (pin "2") (pinfunction "2_2") (pintype "passive"))
    )
    (net (code "22") (name "Net-(K1B-NO)") (class "Default")
      (node (ref "K1") (pin "5") (pinfunction "NO_5") (pintype "passive"))
      (node (ref "R100") (pin "1") (pinfunction "1_1") (pintype "passive"))
      (node (ref "R100") (pin "2") (pinfunction "2_2") (pintype "passive"))
    )
    (net (code "23") (name "Net-(K2A-NO)") (class "Default")
      (node (ref "K2") (pin "4") (pinfunction "NO_4") (pintype "passive"))
      (node (ref "R82") (pin "2") (pintype "passive"))
      (node (ref "R83") (pin "1") (pintype "passive"))
      (node (ref "R87") (pin "2") (pintype "passive"))
      (node (ref "R88") (pin "1") (pintype "passive"))
      (node (ref "R94") (pin "2") (pintype "passive"))
    )
    (net (code "24") (name "Net-(K2B-COM)") (class "Default")
      (node (ref "K2") (pin "6") (pinfunction "COM_6") (pintype "passive"))
      (node (ref "R261") (pin "2") (pintype "passive"))
    )
    (net (code "25") (name "Net-(K2B-NO)") (class "Default")
      (node (ref "K2") (pin "5") (pinfunction "NO_5") (pintype "passive"))
      (node (ref "R96") (pin "1") (pinfunction "1_1") (pintype "passive"))
      (node (ref "R96") (pin "2") (pinfunction "2_2") (pintype "passive"))
    )
    (net (code "26") (name "Net-(Q9-B)") (class "Default")
      (node (ref "Q9") (pin "1") (pinfunction "B_1") (pintype "passive"))
      (node (ref "R106") (pin "2") (pintype "passive"))
    )
    (net (code "27") (name "Net-(Q10-B)") (class "Default")
      (node (ref "Q10") (pin "1") (pinfunction "B_1") (pintype "passive"))
      (node (ref "R108") (pin "2") (pintype "passive"))
    )
    (net (code "28") (name "Net-(R78-Pad2)") (class "Default")
      (node (ref "R78") (pin "2") (pinfunction "2_2") (pintype "passive"))
      (node (ref "R79") (pin "1") (pintype "passive"))
    )
    (net (code "29") (name "Net-(R84-Pad2)") (class "Default")
      (node (ref "R84") (pin "2") (pintype "passive"))
      (node (ref "R85") (pin "1") (pintype "passive"))
    )
    (net (code "30") (name "Net-(R89-Pad2)") (class "Default")
      (node (ref "R89") (pin "2") (pintype "passive"))
      (node (ref "R90") (pin "1") (pintype "passive"))
    )
    (net (code "31") (name "Net-(R91-Pad2)") (class "Default")
      (node (ref "R91") (pin "2") (pintype "passive"))
      (node (ref "R92") (pin "1") (pintype "passive"))
    )
    (net (code "32") (name "Net-(R93-Pad2)") (class "Default")
      (node (ref "R93") (pin "2") (pintype "passive"))
      (node (ref "R99") (pin "3") (pinfunction "3_3") (pintype "passive"))
    )
    (net (code "33") (name "Net-(R94-Pad1)") (class "Default")
      (node (ref "R94") (pin "1") (pintype "passive"))
      (node (ref "R96") (pin "3") (pinfunction "3_3") (pintype "passive"))
    )
    (net (code "34") (name "Net-(R97-Pad2)") (class "Default")
      (node (ref "R97") (pin "2") (pintype "passive"))
      (node (ref "R98") (pin "1") (pintype "passive"))
    )
    (net (code "35") (name "Net-(R100-Pad3)") (class "Default")
      (node (ref "R100") (pin "3") (pinfunction "3_3") (pintype "passive"))
      (node (ref "R95") (pin "1") (pintype "passive"))
    )
    (net (code "36") (name "Net-(R105-Pad2)") (class "Default")
      (node (ref "R105") (pin "2") (pintype "passive"))
      (node (ref "R107") (pin "2") (pinfunction "2_2") (pintype "passive"))
    )
    (net (code "37") (name "Net-(R241-Pad1)") (class "Default")
      (node (ref "R241") (pin "1") (pintype "passive"))
      (node (ref "VR202") (pin "2") (pinfunction "2_2") (pintype "passive"))
    )
    (net (code "38") (name "Net-(R316-Pad1)") (class "Default")
      (node (ref "R316") (pin "1") (pintype "passive"))
      (node (ref "VR211") (pin "2") (pinfunction "2_2") (pintype "passive"))
    )
    (net (code "39") (name "Net-(U11--)") (class "Default")
      (node (ref "R79") (pin "2") (pintype "passive"))
      (node (ref "R80") (pin "1") (pintype "passive"))
      (node (ref "R81") (pin "1") (pintype "passive"))
      (node (ref "R86") (pin "2") (pintype "passive"))
      (node (ref "U11") (pin "2") (pinfunction "-_2") (pintype "passive"))
    )
    (net (code "40") (name "Net-(U13C-Y)") (class "Default")
      (node (ref "R102") (pin "2") (pintype "passive"))
      (node (ref "R103") (pin "1") (pintype "passive"))
      (node (ref "U13") (pin "3") (pinfunction "Y_3") (pintype "passive"))
      (node (ref "U31") (pin "7") (pinfunction "O_7") (pintype "passive"))
    )
    (net (code "41") (name "Net-(U13C-Y1)") (class "Default")
      (node (ref "R101") (pin "1") (pintype "passive"))
      (node (ref "U13") (pin "5") (pinfunction "Y1_5") (pintype "passive"))
      (node (ref "U31") (pin "1") (pinfunction "O_1") (pintype "passive"))
    )
    (net (code "42") (name "Net-(U30B--)") (class "Default")
      (node (ref "R241") (pin "2") (pintype "passive"))
      (node (ref "R242") (pin "1") (pintype "passive"))
      (node (ref "R243") (pin "2") (pintype "passive"))
      (node (ref "U30") (pin "6") (pinfunction "-_6") (pintype "passive"))
    )
    (net (code "43") (name "Net-(U31A--)") (class "Default")
      (node (ref "R101") (pin "2") (pintype "passive"))
      (node (ref "R102") (pin "1") (pintype "passive"))
      (node (ref "R104") (pin "1") (pintype "passive"))
      (node (ref "R105") (pin "1") (pintype "passive"))
      (node (ref "U31") (pin "2") (pinfunction "-_2") (pintype "passive"))
    )
    (net (code "44") (name "Net-(U31B--)") (class "Default")
      (node (ref "R103") (pin "2") (pintype "passive"))
      (node (ref "R261") (pin "1") (pintype "passive"))
      (node (ref "R314") (pin "2") (pintype "passive"))
      (node (ref "R316") (pin "2") (pintype "passive"))
      (node (ref "U31") (pin "6") (pinfunction "-_6") (pintype "passive"))
    )
    (net (code "45") (name "Net-(U32A--)") (class "Default")
      (node (ref "R257") (pin "1") (pintype "passive"))
      (node (ref "R86") (pin "1") (pintype "passive"))
      (node (ref "U32") (pin "1") (pinfunction "O_1") (pintype "passive"))
      (node (ref "U32") (pin "2") (pinfunction "-_2") (pintype "passive"))
    )
    (net (code "46") (name "Net-(U213C-Y1)") (class "Default")
      (node (ref "R242") (pin "2") (pintype "passive"))
      (node (ref "U213") (pin "5") (pinfunction "Y1_5") (pintype "passive"))
      (node (ref "U30") (pin "7") (pinfunction "O_7") (pintype "passive"))
    )
    (net (code "47") (name "Net-(U213C-Y3)") (class "Default")
      (node (ref "U213") (pin "4") (pinfunction "Y3_4") (pintype "passive"))
      (node (ref "U32") (pin "3") (pinfunction "+_3") (pintype "passive"))
    )
    (net (code "48") (name "P5VA") (class "Default")
      (node (ref "C68") (pin "1") (pintype "passive"))
      (node (ref "C69") (pin "1") (pintype "passive"))
      (node (ref "C70") (pin "1") (pintype "passive"))
      (node (ref "D215") (pin "2") (pinfunction "A_2") (pintype "passive"))
      (node (ref "R107") (pin "3") (pinfunction "3_3") (pintype "passive"))
      (node (ref "R78") (pin "3") (pinfunction "3_3") (pintype "passive"))
      (node (ref "U30") (pin "8") (pinfunction "VCC_8") (pintype "passive"))
      (node (ref "U31") (pin "8") (pinfunction "VCC_8") (pintype "passive"))
      (node (ref "U32") (pin "8") (pinfunction "VCC_8") (pintype "passive"))
      (node (ref "VR202") (pin "3") (pinfunction "3_3") (pintype "passive"))
      (node (ref "VR211") (pin "3") (pinfunction "3_3") (pintype "passive"))
    )
    (net (code "49") (name "P5VREL") (class "Default")
      (node (ref "D36") (pin "3") (pinfunction "K_3") (pintype "passive"))
      (node (ref "D37") (pin "3") (pinfunction "K_3") (pintype "passive"))
      (node (ref "K1") (pin "1") (pinfunction "1_1") (pintype "passive"))
      (node (ref "K2") (pin "1") (pinfunction "1_1") (pintype "passive"))
    )
    (net (code "50") (name "P48V") (class "Default")
      (node (ref "D231") (pin "2") (pinfunction "A_2") (pintype "passive"))
    )
    (net (code "51") (name "unconnected-(K1A-NC-Pad2)") (class "Default")
      (node (ref "K1") (pin "2") (pinfunction "NC_2") (pintype "passive"))
    )
    (net (code "52") (name "unconnected-(K2A-NC-Pad2)") (class "Default")
      (node (ref "K2") (pin "2") (pinfunction "NC_2") (pintype "passive"))
    )
  )
)
